# digital_sensor.net
KiCad netlist of a schematic drawn in EAGLE
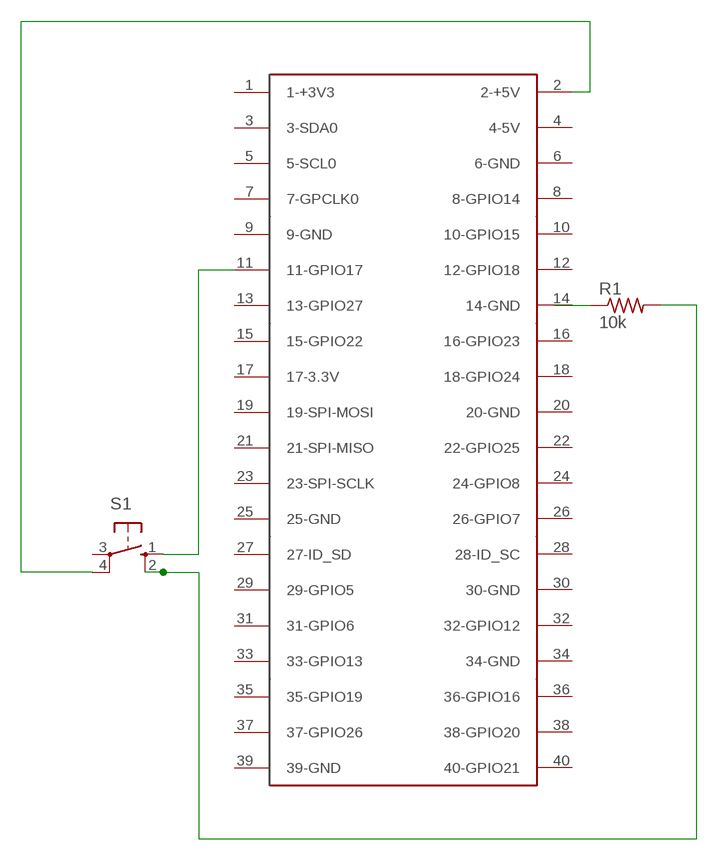
[diagram p0: schematic, sheet 1]

(export (version "E")
  (design (tool "Eeschema 10.0.6"))
  (components
    (comp (ref "R1")
      (value "10k")
      (footprint "eagle-import:0207_12")
      (libsource (lib "eagle-import") (part "R-US_0207/12"))
    )
    (comp (ref "S1")
      (value "40-XX-ROUND")
      (footprint "eagle-import:B3F-40XX-ROUND")
      (libsource (lib "eagle-import") (part "40-XX-ROUND"))
    )
    (comp (ref "U$1")
      (value "RASPBERRY-PI")
      (footprint "eagle-import:RASPBERRY-PI")
      (libsource (lib "eagle-import") (part "RASPBERRY-PI"))
    )
  )
  (nets
    (net (code "1") (name "Net-(S1-P1)") (class "Default")
      (node (ref "S1") (pin "4") (pinfunction "P1_4") (pintype "passive"))
      (node (ref "U$1") (pin "2") (pinfunction "2-+5V_2") (pintype "bidirectional"))
    )
    (net (code "2") (name "Net-(S1-S)") (class "Default")
      (node (ref "S1") (pin "1") (pinfunction "S_1") (pintype "passive"))
      (node (ref "U$1") (pin "11") (pinfunction "11-GPIO17_11") (pintype "bidirectional"))
    )
    (net (code "3") (name "Net-(S1-S1)") (class "Default")
      (node (ref "R1") (pin "2") (pinfunction "2_2") (pintype "passive"))
      (node (ref "S1") (pin "2") (pinfunction "S1_2") (pintype "passive"))
    )
    (net (code "4") (name "unconnected-(R1-Pad1)") (class "Default")
      (node (ref "R1") (pin "1") (pinfunction "1_1") (pintype "passive"))
    )
    (net (code "5") (name "unconnected-(S1-P-Pad3)") (class "Default")
      (node (ref "S1") (pin "3") (pinfunction "P_3") (pintype "passive"))
    )
    (net (code "6") (name "unconnected-(U$1-1-+3V3-Pad1)") (class "Default")
      (node (ref "U$1") (pin "1") (pinfunction "1-+3V3_1") (pintype "bidirectional"))
    )
    (net (code "7") (name "unconnected-(U$1-3-SDA0-Pad3)") (class "Default")
      (node (ref "U$1") (pin "3") (pinfunction "3-SDA0_3") (pintype "bidirectional"))
    )
    (net (code "8") (name "unconnected-(U$1-4-5V-Pad4)") (class "Default")
      (node (ref "U$1") (pin "4") (pinfunction "4-5V_4") (pintype "bidirectional"))
    )
    (net (code "9") (name "unconnected-(U$1-5-SCL0-Pad5)") (class "Default")
      (node (ref "U$1") (pin "5") (pinfunction "5-SCL0_5") (pintype "bidirectional"))
    )
    (net (code "10") (name "unconnected-(U$1-6-GND-Pad6)") (class "Default")
      (node (ref "U$1") (pin "6") (pinfunction "6-GND_6") (pintype "bidirectional"))
    )
    (net (code "11") (name "unconnected-(U$1-7-GPCLK0-Pad7)") (class "Default")
      (node (ref "U$1") (pin "7") (pinfunction "7-GPCLK0_7") (pintype "bidirectional"))
    )
    (net (code "12") (name "unconnected-(U$1-8-GPIO14-Pad8)") (class "Default")
      (node (ref "U$1") (pin "8") (pinfunction "8-GPIO14_8") (pintype "bidirectional"))
    )
    (net (code "13") (name "unconnected-(U$1-9-GND-Pad9)") (class "Default")
      (node (ref "U$1") (pin "9") (pinfunction "9-GND_9") (pintype "bidirectional"))
    )
    (net (code "14") (name "unconnected-(U$1-10-GPIO15-Pad10)") (class "Default")
      (node (ref "U$1") (pin "10") (pinfunction "10-GPIO15_10") (pintype "bidirectional"))
    )
    (net (code "15") (name "unconnected-(U$1-12-GPIO18-Pad12)") (class "Default")
      (node (ref "U$1") (pin "12") (pinfunction "12-GPIO18_12") (pintype "bidirectional"))
    )
    (net (code "16") (name "unconnected-(U$1-13-GPIO27-Pad13)") (class "Default")
      (node (ref "U$1") (pin "13") (pinfunction "13-GPIO27_13") (pintype "bidirectional"))
    )
    (net (code "17") (name "unconnected-(U$1-14-GND-Pad14)") (class "Default")
      (node (ref "U$1") (pin "14") (pinfunction "14-GND_14") (pintype "bidirectional"))
    )
    (net (code "18") (name "unconnected-(U$1-15-GPIO22-Pad15)") (class "Default")
      (node (ref "U$1") (pin "15") (pinfunction "15-GPIO22_15") (pintype "bidirectional"))
    )
    (net (code "19") (name "unconnected-(U$1-16-GPIO23-Pad16)") (class "Default")
      (node (ref "U$1") (pin "16") (pinfunction "16-GPIO23_16") (pintype "bidirectional"))
    )
    (net (code "20") (name "unconnected-(U$1-17-3.3V-Pad17)") (class "Default")
      (node (ref "U$1") (pin "17") (pinfunction "17-3.3V_17") (pintype "bidirectional"))
    )
    (net (code "21") (name "unconnected-(U$1-18-GPIO24-Pad18)") (class "Default")
      (node (ref "U$1") (pin "18") (pinfunction "18-GPIO24_18") (pintype "bidirectional"))
    )
    (net (code "22") (name "unconnected-(U$1-19-SPI-MOSI-Pad19)") (class "Default")
      (node (ref "U$1") (pin "19") (pinfunction "19-SPI-MOSI_19") (pintype "bidirectional"))
    )
    (net (code "23") (name "unconnected-(U$1-20-GND-Pad20)") (class "Default")
      (node (ref "U$1") (pin "20") (pinfunction "20-GND_20") (pintype "bidirectional"))
    )
    (net (code "24") (name "unconnected-(U$1-21-SPI-MISO-Pad21)") (class "Default")
      (node (ref "U$1") (pin "21") (pinfunction "21-SPI-MISO_21") (pintype "bidirectional"))
    )
    (net (code "25") (name "unconnected-(U$1-22-GPIO25-Pad22)") (class "Default")
      (node (ref "U$1") (pin "22") (pinfunction "22-GPIO25_22") (pintype "bidirectional"))
    )
    (net (code "26") (name "unconnected-(U$1-23-SPI-SCLK-Pad23)") (class "Default")
      (node (ref "U$1") (pin "23") (pinfunction "23-SPI-SCLK_23") (pintype "bidirectional"))
    )
    (net (code "27") (name "unconnected-(U$1-24-GPIO8-Pad24)") (class "Default")
      (node (ref "U$1") (pin "24") (pinfunction "24-GPIO8_24") (pintype "bidirectional"))
    )
    (net (code "28") (name "unconnected-(U$1-25-GND-Pad25)") (class "Default")
      (node (ref "U$1") (pin "25") (pinfunction "25-GND_25") (pintype "bidirectional"))
    )
    (net (code "29") (name "unconnected-(U$1-26-GPIO7-Pad26)") (class "Default")
      (node (ref "U$1") (pin "26") (pinfunction "26-GPIO7_26") (pintype "bidirectional"))
    )
    (net (code "30") (name "unconnected-(U$1-27-ID_SD-Pad27)") (class "Default")
      (node (ref "U$1") (pin "27") (pinfunction "27-ID_SD_27") (pintype "bidirectional"))
    )
    (net (code "31") (name "unconnected-(U$1-28-ID_SC-Pad28)") (class "Default")
      (node (ref "U$1") (pin "28") (pinfunction "28-ID_SC_28") (pintype "bidirectional"))
    )
    (net (code "32") (name "unconnected-(U$1-29-GPIO5-Pad29)") (class "Default")
      (node (ref "U$1") (pin "29") (pinfunction "29-GPIO5_29") (pintype "bidirectional"))
    )
    (net (code "33") (name "unconnected-(U$1-30-GND-Pad30)") (class "Default")
      (node (ref "U$1") (pin "30") (pinfunction "30-GND_30") (pintype "bidirectional"))
    )
    (net (code "34") (name "unconnected-(U$1-31-GPIO6-Pad31)") (class "Default")
      (node (ref "U$1") (pin "31") (pinfunction "31-GPIO6_31") (pintype "bidirectional"))
    )
    (net (code "35") (name "unconnected-(U$1-32-GPIO12-Pad32)") (class "Default")
      (node (ref "U$1") (pin "32") (pinfunction "32-GPIO12_32") (pintype "bidirectional"))
    )
    (net (code "36") (name "unconnected-(U$1-33-GPIO13-Pad33)") (class "Default")
      (node (ref "U$1") (pin "33") (pinfunction "33-GPIO13_33") (pintype "bidirectional"))
    )
    (net (code "37") (name "unconnected-(U$1-34-GND-Pad34)") (class "Default")
      (node (ref "U$1") (pin "34") (pinfunction "34-GND_34") (pintype "bidirectional"))
    )
    (net (code "38") (name "unconnected-(U$1-35-GPIO19-Pad35)") (class "Default")
      (node (ref "U$1") (pin "35") (pinfunction "35-GPIO19_35") (pintype "bidirectional"))
    )
    (net (code "39") (name "unconnected-(U$1-36-GPIO16-Pad36)") (class "Default")
      (node (ref "U$1") (pin "36") (pinfunction "36-GPIO16_36") (pintype "bidirectional"))
    )
    (net (code "40") (name "unconnected-(U$1-37-GPIO26-Pad37)") (class "Default")
      (node (ref "U$1") (pin "37") (pinfunction "37-GPIO26_37") (pintype "bidirectional"))
    )
    (net (code "41") (name "unconnected-(U$1-38-GPIO20-Pad38)") (class "Default")
      (node (ref "U$1") (pin "38") (pinfunction "38-GPIO20_38") (pintype "bidirectional"))
    )
    (net (code "42") (name "unconnected-(U$1-39-GND-Pad39)") (class "Default")
      (node (ref "U$1") (pin "39") (pinfunction "39-GND_39") (pintype "bidirectional"))
    )
    (net (code "43") (name "unconnected-(U$1-40-GPIO21-Pad40)") (class "Default")
      (node (ref "U$1") (pin "40") (pinfunction "40-GPIO21_40") (pintype "bidirectional"))
    )
  )
)
